# MotorDriver.net
KiCad netlist of a schematic drawn in Altium Designer
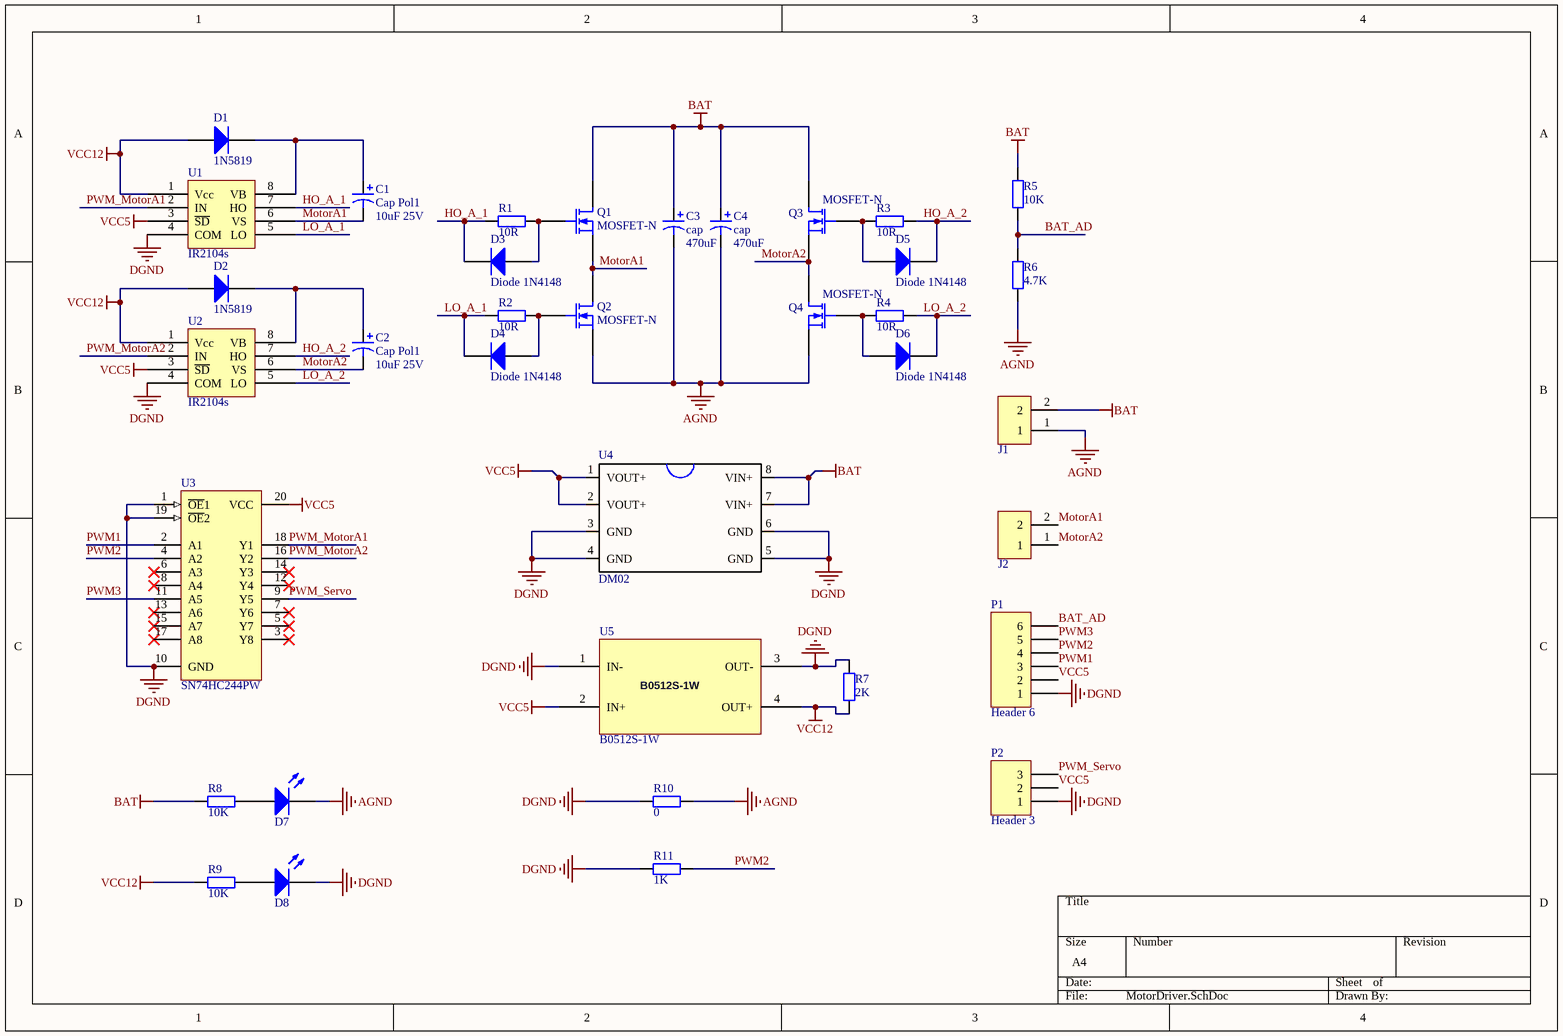
[diagram p0: MotorDriver.SchDoc]

(export (version "E")
  (design (tool "Eeschema 10.0.6"))
  (components
    (comp (ref "C1")
      (value "Cap Pol1")
      (footprint "Cap 3528B")
      (description "Polarized Capacitor (Radial)")
      (fields (field (name "ALTIUM_VALUE") "10uF 25V") (field (name "PUBLISHER") "Altium Limited"))
      (libsource (lib "Miscellaneous Devices") (part "Cap Pol1"))
    )
    (comp (ref "C2")
      (value "Cap Pol1")
      (footprint "Cap 3528B")
      (description "Polarized Capacitor (Radial)")
      (fields (field (name "ALTIUM_VALUE") "10uF 25V") (field (name "PUBLISHER") "Altium Limited"))
      (libsource (lib "Miscellaneous Devices") (part "Cap Pol1"))
    )
    (comp (ref "C3")
      (value "cap")
      (footprint "cap贴片铝电解质470uF 16V")
      (fields (field (name "ALTIUM_VALUE") "470uF"))
      (libsource (lib "文的集成库") (part "cap"))
    )
    (comp (ref "C4")
      (value "cap")
      (footprint "cap贴片铝电解质470uF 16V")
      (fields (field (name "ALTIUM_VALUE") "470uF"))
      (libsource (lib "文的集成库") (part "cap"))
    )
    (comp (ref "D1") (value "1N5819") (footprint "DIO-214") (libsource (lib "钦的集成库1") (part "1N4007")))
    (comp (ref "D2") (value "1N5819") (footprint "DIO-214") (libsource (lib "钦的集成库1") (part "1N4007")))
    (comp (ref "D3")
      (value "Diode 1N4148")
      (footprint "0805")
      (description "High Conductance Fast Diode")
      (fields (field (name "PUBLISHER") "Altium Limited"))
      (libsource (lib "Miscellaneous Devices") (part "Diode 1N4148"))
    )
    (comp (ref "D4")
      (value "Diode 1N4148")
      (footprint "0805")
      (description "High Conductance Fast Diode")
      (fields (field (name "PUBLISHER") "Altium Limited"))
      (libsource (lib "Miscellaneous Devices") (part "Diode 1N4148"))
    )
    (comp (ref "D5")
      (value "Diode 1N4148")
      (footprint "0805")
      (description "High Conductance Fast Diode")
      (fields (field (name "PUBLISHER") "Altium Limited"))
      (libsource (lib "Miscellaneous Devices") (part "Diode 1N4148"))
    )
    (comp (ref "D6")
      (value "Diode 1N4148")
      (footprint "0805")
      (description "High Conductance Fast Diode")
      (fields (field (name "PUBLISHER") "Altium Limited"))
      (libsource (lib "Miscellaneous Devices") (part "Diode 1N4148"))
    )
    (comp (ref "D7") (value "12V") (footprint "LED_0805") (libsource (lib "钦的集成库1") (part "LED_")))
    (comp (ref "D8") (value "12V") (footprint "LED_0805") (libsource (lib "钦的集成库1") (part "LED_")))
    (comp (ref "J1") (value "接线端子2P") (footprint "接线端子KF301-2P") (libsource (lib "钦的集成库1") (part "接线端子2P")))
    (comp (ref "J2") (value "接线端子2P") (footprint "接线端子KF301-2P") (libsource (lib "钦的集成库1") (part "接线端子2P")))
    (comp (ref "P1")
      (value "Header 6")
      (footprint "HDR1X6")
      (description "Header, 6-Pin")
      (fields (field (name "PUBLISHER") "Altium Limited"))
      (libsource (lib "Miscellaneous Connectors") (part "Header 6"))
    )
    (comp (ref "P2")
      (value "Header 3")
      (footprint "HDR1X3")
      (description "Header, 3-Pin")
      (fields (field (name "PUBLISHER") "Altium Limited"))
      (libsource (lib "Miscellaneous Connectors") (part "Header 3"))
    )
    (comp (ref "Q1")
      (value "MOSFET-N")
      (footprint "TO-252")
      (description "N-Channel MOSFET")
      (fields (field (name "PUBLISHER") "Altium Limited"))
      (libsource (lib "Miscellaneous Devices") (part "MOSFET-N"))
    )
    (comp (ref "Q2")
      (value "MOSFET-N")
      (footprint "TO-252")
      (description "N-Channel MOSFET")
      (fields (field (name "PUBLISHER") "Altium Limited"))
      (libsource (lib "Miscellaneous Devices") (part "MOSFET-N"))
    )
    (comp (ref "Q3")
      (value "MOSFET-N")
      (footprint "TO-252")
      (description "N-Channel MOSFET")
      (fields (field (name "PUBLISHER") "Altium Limited"))
      (libsource (lib "Miscellaneous Devices") (part "MOSFET-N"))
    )
    (comp (ref "Q4")
      (value "MOSFET-N")
      (footprint "TO-252")
      (description "N-Channel MOSFET")
      (fields (field (name "PUBLISHER") "Altium Limited"))
      (libsource (lib "Miscellaneous Devices") (part "MOSFET-N"))
    )
    (comp (ref "R1")
      (value "10R")
      (footprint "0805")
      (fields (field (name "Comment") "Res_"))
      (libsource (lib "钦的集成库1") (part "Res_"))
    )
    (comp (ref "R2")
      (value "10R")
      (footprint "0805")
      (fields (field (name "Comment") "Res_"))
      (libsource (lib "钦的集成库1") (part "Res_"))
    )
    (comp (ref "R3")
      (value "10R")
      (footprint "0805")
      (fields (field (name "Comment") "Res_"))
      (libsource (lib "钦的集成库1") (part "Res_"))
    )
    (comp (ref "R4")
      (value "10R")
      (footprint "0805")
      (fields (field (name "Comment") "Res_"))
      (libsource (lib "钦的集成库1") (part "Res_"))
    )
    (comp (ref "R5")
      (value "10K")
      (footprint "0805")
      (fields (field (name "Comment") "Res_"))
      (libsource (lib "") (part "Res__1"))
    )
    (comp (ref "R6")
      (value "4.7K")
      (footprint "0805")
      (fields (field (name "Comment") "Res_"))
      (libsource (lib "") (part "Res__1"))
    )
    (comp (ref "R7")
      (value "2K")
      (footprint "0805")
      (fields (field (name "Comment") "Res_"))
      (libsource (lib "") (part "Res__2"))
    )
    (comp (ref "R8")
      (value "10K")
      (footprint "0805")
      (fields (field (name "Comment") "Res_"))
      (libsource (lib "钦的集成库1") (part "Res_"))
    )
    (comp (ref "R9")
      (value "10K")
      (footprint "0805")
      (fields (field (name "Comment") "Res_"))
      (libsource (lib "钦的集成库1") (part "Res_"))
    )
    (comp (ref "R10")
      (value "0")
      (footprint "1206")
      (fields (field (name "Comment") "Res_"))
      (libsource (lib "钦的集成库1") (part "Res_"))
    )
    (comp (ref "R11")
      (value "1K")
      (footprint "0805")
      (fields (field (name "Comment") "Res_"))
      (libsource (lib "钦的集成库1") (part "Res_"))
    )
    (comp (ref "U1") (value "IR2104s") (footprint "IR2104-SOIC8") (libsource (lib "Schlib1") (part "2014s")))
    (comp (ref "U2") (value "IR2104s") (footprint "IR2104-SOIC8") (libsource (lib "Schlib1") (part "2014s")))
    (comp (ref "U3")
      (value "SN74HC244PW")
      (footprint "74HC244-TSOP")
      (description "Octal Buffer/Driver with 3-State Outputs")
      (fields (field (name "PUBLISHER") "Altium Limited"))
      (libsource (lib "驱动") (part "SN74LVC244APW"))
    )
    (comp (ref "U4")
      (value "DM02")
      (footprint "DM02")
      (description "DC-DC 5V")
      (libsource (lib "自动化研究所原理图库") (part "DM02"))
    )
    (comp (ref "U5") (value "B0512S-1W") (footprint "B0512S-1W") (libsource (lib "文的集成库") (part "B0512S-1W")))
  )
  (nets
    (net (code "1") (name "/BAT_AD") (class "Default")
      (node (ref "P1") (pin "6") (pinfunction "6_6") (pintype "passive"))
      (node (ref "R5") (pin "1") (pinfunction "1_1") (pintype "passive"))
      (node (ref "R6") (pin "2") (pinfunction "2_2") (pintype "passive"))
    )
    (net (code "2") (name "/HO_A_1") (class "Default")
      (node (ref "D3") (pin "2") (pinfunction "K_2") (pintype "passive"))
      (node (ref "R1") (pin "1") (pinfunction "1_1") (pintype "passive"))
      (node (ref "U1") (pin "7") (pinfunction "HO_7") (pintype "passive"))
    )
    (net (code "3") (name "/HO_A_2") (class "Default")
      (node (ref "D5") (pin "2") (pinfunction "K_2") (pintype "passive"))
      (node (ref "R3") (pin "2") (pinfunction "2_2") (pintype "passive"))
      (node (ref "U2") (pin "7") (pinfunction "HO_7") (pintype "passive"))
    )
    (net (code "4") (name "/LO_A_1") (class "Default")
      (node (ref "D4") (pin "2") (pinfunction "K_2") (pintype "passive"))
      (node (ref "R2") (pin "1") (pinfunction "1_1") (pintype "passive"))
      (node (ref "U1") (pin "5") (pinfunction "LO_5") (pintype "passive"))
    )
    (net (code "5") (name "/LO_A_2") (class "Default")
      (node (ref "D6") (pin "2") (pinfunction "K_2") (pintype "passive"))
      (node (ref "R4") (pin "2") (pinfunction "2_2") (pintype "passive"))
      (node (ref "U2") (pin "5") (pinfunction "LO_5") (pintype "passive"))
    )
    (net (code "6") (name "/MotorA1") (class "Default")
      (node (ref "C1") (pin "2") (pinfunction "2_2") (pintype "passive"))
      (node (ref "J2") (pin "2") (pinfunction "2_2") (pintype "power_in"))
      (node (ref "Q1") (pin "3") (pinfunction "S_3") (pintype "passive"))
      (node (ref "Q2") (pin "1") (pinfunction "D_1") (pintype "passive"))
      (node (ref "U1") (pin "6") (pinfunction "VS_6") (pintype "passive"))
    )
    (net (code "7") (name "/MotorA2") (class "Default")
      (node (ref "C2") (pin "2") (pinfunction "2_2") (pintype "passive"))
      (node (ref "J2") (pin "1") (pinfunction "1_1") (pintype "power_in"))
      (node (ref "Q3") (pin "3") (pinfunction "S_3") (pintype "passive"))
      (node (ref "Q4") (pin "1") (pinfunction "D_1") (pintype "passive"))
      (node (ref "U2") (pin "6") (pinfunction "VS_6") (pintype "passive"))
    )
    (net (code "8") (name "/PWM1") (class "Default")
      (node (ref "P1") (pin "3") (pinfunction "3_3") (pintype "passive"))
      (node (ref "U3") (pin "2") (pinfunction "A1_2") (pintype "passive"))
    )
    (net (code "9") (name "/PWM2") (class "Default")
      (node (ref "P1") (pin "4") (pinfunction "4_4") (pintype "passive"))
      (node (ref "R11") (pin "2") (pinfunction "2_2") (pintype "passive"))
      (node (ref "U3") (pin "4") (pinfunction "A2_4") (pintype "passive"))
    )
    (net (code "10") (name "/PWM3") (class "Default")
      (node (ref "P1") (pin "5") (pinfunction "5_5") (pintype "passive"))
      (node (ref "U3") (pin "11") (pinfunction "A5_11") (pintype "passive"))
    )
    (net (code "11") (name "/PWM_MotorA1") (class "Default")
      (node (ref "U1") (pin "2") (pinfunction "IN_2") (pintype "passive"))
      (node (ref "U3") (pin "18") (pinfunction "Y1_18") (pintype "tri_state"))
    )
    (net (code "12") (name "/PWM_MotorA2") (class "Default")
      (node (ref "U2") (pin "2") (pinfunction "IN_2") (pintype "passive"))
      (node (ref "U3") (pin "16") (pinfunction "Y2_16") (pintype "tri_state"))
    )
    (net (code "13") (name "/PWM_Servo") (class "Default")
      (node (ref "P2") (pin "3") (pinfunction "3_3") (pintype "passive"))
      (node (ref "U3") (pin "9") (pinfunction "Y5_9") (pintype "tri_state"))
    )
    (net (code "14") (name "AGND") (class "Default")
      (node (ref "C3") (pin "2") (pinfunction "2_2") (pintype "passive"))
      (node (ref "C4") (pin "2") (pinfunction "2_2") (pintype "passive"))
      (node (ref "D7") (pin "2") (pinfunction "K_2") (pintype "passive"))
      (node (ref "J1") (pin "1") (pinfunction "1_1") (pintype "power_in"))
      (node (ref "Q2") (pin "3") (pinfunction "S_3") (pintype "passive"))
      (node (ref "Q4") (pin "3") (pinfunction "S_3") (pintype "passive"))
      (node (ref "R10") (pin "2") (pinfunction "2_2") (pintype "passive"))
      (node (ref "R6") (pin "1") (pinfunction "1_1") (pintype "passive"))
    )
    (net (code "15") (name "BAT") (class "Default")
      (node (ref "C3") (pin "1") (pinfunction "1_1") (pintype "passive"))
      (node (ref "C4") (pin "1") (pinfunction "1_1") (pintype "passive"))
      (node (ref "J1") (pin "2") (pinfunction "2_2") (pintype "power_in"))
      (node (ref "Q1") (pin "1") (pinfunction "D_1") (pintype "passive"))
      (node (ref "Q3") (pin "1") (pinfunction "D_1") (pintype "passive"))
      (node (ref "R5") (pin "2") (pinfunction "2_2") (pintype "passive"))
      (node (ref "R8") (pin "1") (pinfunction "1_1") (pintype "passive"))
      (node (ref "U4") (pin "7") (pinfunction "VIN+_7") (pintype "passive"))
      (node (ref "U4") (pin "8") (pinfunction "VIN+_8") (pintype "passive"))
    )
    (net (code "16") (name "DGND") (class "Default")
      (node (ref "D8") (pin "2") (pinfunction "K_2") (pintype "passive"))
      (node (ref "P1") (pin "1") (pinfunction "1_1") (pintype "passive"))
      (node (ref "P2") (pin "1") (pinfunction "1_1") (pintype "passive"))
      (node (ref "R10") (pin "1") (pinfunction "1_1") (pintype "passive"))
      (node (ref "R11") (pin "1") (pinfunction "1_1") (pintype "passive"))
      (node (ref "R7") (pin "1") (pinfunction "1_1") (pintype "passive"))
      (node (ref "U1") (pin "4") (pinfunction "COM_4") (pintype "passive"))
      (node (ref "U2") (pin "4") (pinfunction "COM_4") (pintype "passive"))
      (node (ref "U3") (pin "1") (pinfunction "~{OE}1_1") (pintype "input"))
      (node (ref "U3") (pin "10") (pinfunction "GND_10") (pintype "power_in"))
      (node (ref "U3") (pin "19") (pinfunction "~{OE}2_19") (pintype "input"))
      (node (ref "U4") (pin "3") (pinfunction "GND_3") (pintype "passive"))
      (node (ref "U4") (pin "4") (pinfunction "GND_4") (pintype "passive"))
      (node (ref "U4") (pin "5") (pinfunction "GND_5") (pintype "passive"))
      (node (ref "U4") (pin "6") (pinfunction "GND_6") (pintype "passive"))
      (node (ref "U5") (pin "1") (pinfunction "IN-_1") (pintype "passive"))
      (node (ref "U5") (pin "3") (pinfunction "OUT-_3") (pintype "passive"))
    )
    (net (code "17") (name "Net-(D1-K)") (class "Default")
      (node (ref "C1") (pin "1") (pinfunction "1_1") (pintype "passive"))
      (node (ref "D1") (pin "2") (pinfunction "K_2") (pintype "passive"))
      (node (ref "U1") (pin "8") (pinfunction "VB_8") (pintype "passive"))
    )
    (net (code "18") (name "Net-(D2-K)") (class "Default")
      (node (ref "C2") (pin "1") (pinfunction "1_1") (pintype "passive"))
      (node (ref "D2") (pin "2") (pinfunction "K_2") (pintype "passive"))
      (node (ref "U2") (pin "8") (pinfunction "VB_8") (pintype "passive"))
    )
    (net (code "19") (name "Net-(D3-A)") (class "Default")
      (node (ref "D3") (pin "1") (pinfunction "A_1") (pintype "passive"))
      (node (ref "Q1") (pin "2") (pinfunction "G_2") (pintype "passive"))
      (node (ref "R1") (pin "2") (pinfunction "2_2") (pintype "passive"))
    )
    (net (code "20") (name "Net-(D4-A)") (class "Default")
      (node (ref "D4") (pin "1") (pinfunction "A_1") (pintype "passive"))
      (node (ref "Q2") (pin "2") (pinfunction "G_2") (pintype "passive"))
      (node (ref "R2") (pin "2") (pinfunction "2_2") (pintype "passive"))
    )
    (net (code "21") (name "Net-(D5-A)") (class "Default")
      (node (ref "D5") (pin "1") (pinfunction "A_1") (pintype "passive"))
      (node (ref "Q3") (pin "2") (pinfunction "G_2") (pintype "passive"))
      (node (ref "R3") (pin "1") (pinfunction "1_1") (pintype "passive"))
    )
    (net (code "22") (name "Net-(D6-A)") (class "Default")
      (node (ref "D6") (pin "1") (pinfunction "A_1") (pintype "passive"))
      (node (ref "Q4") (pin "2") (pinfunction "G_2") (pintype "passive"))
      (node (ref "R4") (pin "1") (pinfunction "1_1") (pintype "passive"))
    )
    (net (code "23") (name "Net-(D7-A)") (class "Default")
      (node (ref "D7") (pin "1") (pinfunction "A_1") (pintype "passive"))
      (node (ref "R8") (pin "2") (pinfunction "2_2") (pintype "passive"))
    )
    (net (code "24") (name "Net-(D8-A)") (class "Default")
      (node (ref "D8") (pin "1") (pinfunction "A_1") (pintype "passive"))
      (node (ref "R9") (pin "2") (pinfunction "2_2") (pintype "passive"))
    )
    (net (code "25") (name "VCC5") (class "Default")
      (node (ref "P1") (pin "2") (pinfunction "2_2") (pintype "passive"))
      (node (ref "P2") (pin "2") (pinfunction "2_2") (pintype "passive"))
      (node (ref "U1") (pin "3") (pinfunction "~{SD}_3") (pintype "passive"))
      (node (ref "U2") (pin "3") (pinfunction "~{SD}_3") (pintype "passive"))
      (node (ref "U3") (pin "20") (pinfunction "VCC_20") (pintype "power_in"))
      (node (ref "U4") (pin "1") (pinfunction "VOUT+_1") (pintype "passive"))
      (node (ref "U4") (pin "2") (pinfunction "VOUT+_2") (pintype "passive"))
      (node (ref "U5") (pin "2") (pinfunction "IN+_2") (pintype "passive"))
    )
    (net (code "26") (name "VCC12") (class "Default")
      (node (ref "D1") (pin "1") (pinfunction "A_1") (pintype "passive"))
      (node (ref "D2") (pin "1") (pinfunction "A_1") (pintype "passive"))
      (node (ref "R7") (pin "2") (pinfunction "2_2") (pintype "passive"))
      (node (ref "R9") (pin "1") (pinfunction "1_1") (pintype "passive"))
      (node (ref "U1") (pin "1") (pinfunction "Vcc_1") (pintype "passive"))
      (node (ref "U2") (pin "1") (pinfunction "Vcc_1") (pintype "passive"))
      (node (ref "U5") (pin "4") (pinfunction "OUT+_4") (pintype "passive"))
    )
    (net (code "27") (name "unconnected-(U3-A3-Pad6)") (class "Default")
      (node (ref "U3") (pin "6") (pinfunction "A3_6") (pintype "passive+no_connect"))
    )
    (net (code "28") (name "unconnected-(U3-A4-Pad8)") (class "Default")
      (node (ref "U3") (pin "8") (pinfunction "A4_8") (pintype "passive+no_connect"))
    )
    (net (code "29") (name "unconnected-(U3-A6-Pad13)") (class "Default")
      (node (ref "U3") (pin "13") (pinfunction "A6_13") (pintype "passive+no_connect"))
    )
    (net (code "30") (name "unconnected-(U3-A7-Pad15)") (class "Default")
      (node (ref "U3") (pin "15") (pinfunction "A7_15") (pintype "passive+no_connect"))
    )
    (net (code "31") (name "unconnected-(U3-A8-Pad17)") (class "Default")
      (node (ref "U3") (pin "17") (pinfunction "A8_17") (pintype "passive+no_connect"))
    )
    (net (code "32") (name "unconnected-(U3-Y3-Pad14)") (class "Default")
      (node (ref "U3") (pin "14") (pinfunction "Y3_14") (pintype "tri_state+no_connect"))
    )
    (net (code "33") (name "unconnected-(U3-Y4-Pad12)") (class "Default")
      (node (ref "U3") (pin "12") (pinfunction "Y4_12") (pintype "tri_state+no_connect"))
    )
    (net (code "34") (name "unconnected-(U3-Y6-Pad7)") (class "Default")
      (node (ref "U3") (pin "7") (pinfunction "Y6_7") (pintype "tri_state+no_connect"))
    )
    (net (code "35") (name "unconnected-(U3-Y7-Pad5)") (class "Default")
      (node (ref "U3") (pin "5") (pinfunction "Y7_5") (pintype "tri_state+no_connect"))
    )
    (net (code "36") (name "unconnected-(U3-Y8-Pad3)") (class "Default")
      (node (ref "U3") (pin "3") (pinfunction "Y8_3") (pintype "tri_state+no_connect"))
    )
  )
)
